# ZYNQ_PL_Bank_13.net
KiCad netlist of a schematic drawn in Altium Designer
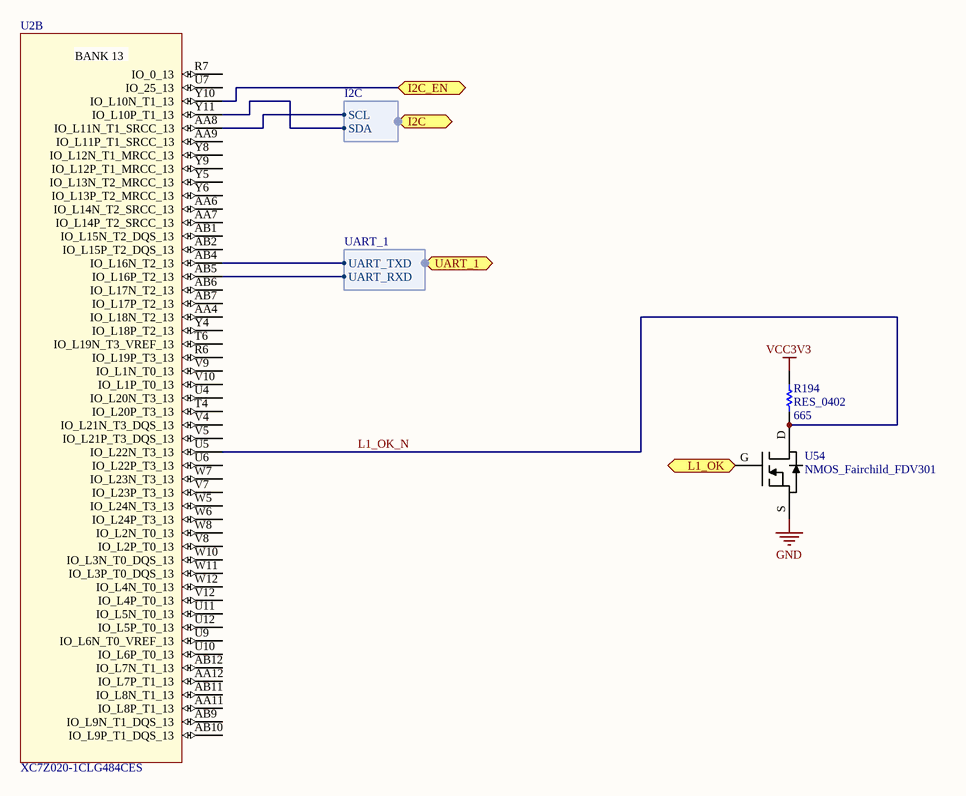
[diagram p0: ZYNQ_PL_Bank_13.SchDoc]

(export (version "E")
  (design (tool "Eeschema 10.0.6"))
  (components
    (comp (ref "R194")
      (value "RES_0402")
      (footprint "RESC0402(1005)_N")
      (description "RES 665 OHM 1/10W 1% 0402 SMD")
      (fields
        (field (name "ALTIUM_VALUE") "665")
        (field (name "PART NUMBER") "ERJ-2RKF6650X")
        (field (name "MANUFACTURER") "Panasonic Electronic Components")
      )
      (libsource (lib "COMRAD_Database") (part "RES_0402"))
    )
    (comp (ref "U2")
      (value "XC7Z020-1CLG484CES")
      (footprint "ZYNQ_xc7z020clg484pkg_BGA-484")
      (description "XC7Z020-1CLG484CES, Zynq-7000 All Programmable SoC")
      (fields (field (name "MANUFACTURER") "Xilinx"))
      (libsource (lib "COMRAD_Database") (part "ZYNQ_XC7Z020CLG484PKG"))
    )
    (comp (ref "U54")
      (value "NMOS_Fairchild_FDV301")
      (footprint "NMOS_Fairchild_FDV301_SOT23-3")
      (description "MOSFET N-CH 25V 220MA SOT-23")
      (fields (field (name "PART NUMBER") "FDV301N") (field (name "MANUFACTURER") "Fairchild Semiconductor"))
      (libsource (lib "COMRAD_Database") (part "NMOS_Fairchild_FDV301"))
    )
  )
  (nets
    (net (code "3") (name "/I2C_EN") (class "Default")
      (node (ref "U2") (pin "Y10") (pinfunction "IO_L10N_T1_13_Y10") (pintype "bidirectional"))
    )
    (net (code "4") (name "/L1_OK") (class "Default") (node (ref "U54") (pin "G") (pintype "passive")))
    (net (code "5") (name "/L1_OK_N") (class "Default")
      (node (ref "R194") (pin "1") (pinfunction "1_1") (pintype "passive"))
      (node (ref "U2") (pin "U5") (pinfunction "IO_L22N_T3_13_U5") (pintype "bidirectional"))
      (node (ref "U54") (pin "D") (pintype "passive"))
    )
    (net (code "6") (name "/SCL") (class "Default")
      (node (ref "U2") (pin "AA8") (pinfunction "IO_L11N_T1_SRCC_13_AA8") (pintype "bidirectional"))
    )
    (net (code "7") (name "/SDA") (class "Default")
      (node (ref "U2") (pin "Y11") (pinfunction "IO_L10P_T1_13_Y11") (pintype "bidirectional"))
    )
    (net (code "8") (name "/UART_RXD") (class "Default")
      (node (ref "U2") (pin "AB5") (pinfunction "IO_L16P_T2_13_AB5") (pintype "bidirectional"))
    )
    (net (code "9") (name "/UART_TXD") (class "Default")
      (node (ref "U2") (pin "AB4") (pinfunction "IO_L16N_T2_13_AB4") (pintype "bidirectional"))
    )
    (net (code "12") (name "GND") (class "Default") (node (ref "U54") (pin "S") (pintype "passive")))
    (net (code "13") (name "VCC3V3") (class "Default")
      (node (ref "R194") (pin "2") (pinfunction "2_2") (pintype "passive"))
    )
    (net (code "14") (name "unconnected-(U2B-IO_0_13-PadR7)") (class "Default")
      (node (ref "U2") (pin "R7") (pinfunction "IO_0_13_R7") (pintype "bidirectional"))
    )
    (net (code "15") (name "unconnected-(U2B-IO_25_13-PadU7)") (class "Default")
      (node (ref "U2") (pin "U7") (pinfunction "IO_25_13_U7") (pintype "bidirectional"))
    )
    (net (code "16") (name "unconnected-(U2B-IO_L1N_T0_13-PadV9)") (class "Default")
      (node (ref "U2") (pin "V9") (pinfunction "IO_L1N_T0_13_V9") (pintype "bidirectional"))
    )
    (net (code "17") (name "unconnected-(U2B-IO_L1P_T0_13-PadV10)") (class "Default")
      (node (ref "U2") (pin "V10") (pinfunction "IO_L1P_T0_13_V10") (pintype "bidirectional"))
    )
    (net (code "18") (name "unconnected-(U2B-IO_L2N_T0_13-PadW8)") (class "Default")
      (node (ref "U2") (pin "W8") (pinfunction "IO_L2N_T0_13_W8") (pintype "bidirectional"))
    )
    (net (code "19") (name "unconnected-(U2B-IO_L2P_T0_13-PadV8)") (class "Default")
      (node (ref "U2") (pin "V8") (pinfunction "IO_L2P_T0_13_V8") (pintype "bidirectional"))
    )
    (net (code "20") (name "unconnected-(U2B-IO_L3N_T0_DQS_13-PadW10)") (class "Default")
      (node (ref "U2") (pin "W10") (pinfunction "IO_L3N_T0_DQS_13_W10") (pintype "bidirectional"))
    )
    (net (code "21") (name "unconnected-(U2B-IO_L3P_T0_DQS_13-PadW11)") (class "Default")
      (node (ref "U2") (pin "W11") (pinfunction "IO_L3P_T0_DQS_13_W11") (pintype "bidirectional"))
    )
    (net (code "22") (name "unconnected-(U2B-IO_L4N_T0_13-PadW12)") (class "Default")
      (node (ref "U2") (pin "W12") (pinfunction "IO_L4N_T0_13_W12") (pintype "bidirectional"))
    )
    (net (code "23") (name "unconnected-(U2B-IO_L4P_T0_13-PadV12)") (class "Default")
      (node (ref "U2") (pin "V12") (pinfunction "IO_L4P_T0_13_V12") (pintype "bidirectional"))
    )
    (net (code "24") (name "unconnected-(U2B-IO_L5N_T0_13-PadU11)") (class "Default")
      (node (ref "U2") (pin "U11") (pinfunction "IO_L5N_T0_13_U11") (pintype "bidirectional"))
    )
    (net (code "25") (name "unconnected-(U2B-IO_L5P_T0_13-PadU12)") (class "Default")
      (node (ref "U2") (pin "U12") (pinfunction "IO_L5P_T0_13_U12") (pintype "bidirectional"))
    )
    (net (code "26") (name "unconnected-(U2B-IO_L6N_T0_VREF_13-PadU9)") (class "Default")
      (node (ref "U2") (pin "U9") (pinfunction "IO_L6N_T0_VREF_13_U9") (pintype "bidirectional"))
    )
    (net (code "27") (name "unconnected-(U2B-IO_L6P_T0_13-PadU10)") (class "Default")
      (node (ref "U2") (pin "U10") (pinfunction "IO_L6P_T0_13_U10") (pintype "bidirectional"))
    )
    (net (code "28") (name "unconnected-(U2B-IO_L7N_T1_13-PadAB12)") (class "Default")
      (node (ref "U2") (pin "AB12") (pinfunction "IO_L7N_T1_13_AB12") (pintype "bidirectional"))
    )
    (net (code "29") (name "unconnected-(U2B-IO_L7P_T1_13-PadAA12)") (class "Default")
      (node (ref "U2") (pin "AA12") (pinfunction "IO_L7P_T1_13_AA12") (pintype "bidirectional"))
    )
    (net (code "30") (name "unconnected-(U2B-IO_L8N_T1_13-PadAB11)") (class "Default")
      (node (ref "U2") (pin "AB11") (pinfunction "IO_L8N_T1_13_AB11") (pintype "bidirectional"))
    )
    (net (code "31") (name "unconnected-(U2B-IO_L8P_T1_13-PadAA11)") (class "Default")
      (node (ref "U2") (pin "AA11") (pinfunction "IO_L8P_T1_13_AA11") (pintype "bidirectional"))
    )
    (net (code "32") (name "unconnected-(U2B-IO_L9N_T1_DQS_13-PadAB9)") (class "Default")
      (node (ref "U2") (pin "AB9") (pinfunction "IO_L9N_T1_DQS_13_AB9") (pintype "bidirectional"))
    )
    (net (code "33") (name "unconnected-(U2B-IO_L9P_T1_DQS_13-PadAB10)") (class "Default")
      (node (ref "U2") (pin "AB10") (pinfunction "IO_L9P_T1_DQS_13_AB10") (pintype "bidirectional"))
    )
    (net (code "34") (name "unconnected-(U2B-IO_L11P_T1_SRCC_13-PadAA9)") (class "Default")
      (node (ref "U2") (pin "AA9") (pinfunction "IO_L11P_T1_SRCC_13_AA9") (pintype "bidirectional"))
    )
    (net (code "35") (name "unconnected-(U2B-IO_L12N_T1_MRCC_13-PadY8)") (class "Default")
      (node (ref "U2") (pin "Y8") (pinfunction "IO_L12N_T1_MRCC_13_Y8") (pintype "bidirectional"))
    )
    (net (code "36") (name "unconnected-(U2B-IO_L12P_T1_MRCC_13-PadY9)") (class "Default")
      (node (ref "U2") (pin "Y9") (pinfunction "IO_L12P_T1_MRCC_13_Y9") (pintype "bidirectional"))
    )
    (net (code "37") (name "unconnected-(U2B-IO_L13N_T2_MRCC_13-PadY5)") (class "Default")
      (node (ref "U2") (pin "Y5") (pinfunction "IO_L13N_T2_MRCC_13_Y5") (pintype "bidirectional"))
    )
    (net (code "38") (name "unconnected-(U2B-IO_L13P_T2_MRCC_13-PadY6)") (class "Default")
      (node (ref "U2") (pin "Y6") (pinfunction "IO_L13P_T2_MRCC_13_Y6") (pintype "bidirectional"))
    )
    (net (code "39") (name "unconnected-(U2B-IO_L14N_T2_SRCC_13-PadAA6)") (class "Default")
      (node (ref "U2") (pin "AA6") (pinfunction "IO_L14N_T2_SRCC_13_AA6") (pintype "bidirectional"))
    )
    (net (code "40") (name "unconnected-(U2B-IO_L14P_T2_SRCC_13-PadAA7)") (class "Default")
      (node (ref "U2") (pin "AA7") (pinfunction "IO_L14P_T2_SRCC_13_AA7") (pintype "bidirectional"))
    )
    (net (code "41") (name "unconnected-(U2B-IO_L15N_T2_DQS_13-PadAB1)") (class "Default")
      (node (ref "U2") (pin "AB1") (pinfunction "IO_L15N_T2_DQS_13_AB1") (pintype "bidirectional"))
    )
    (net (code "42") (name "unconnected-(U2B-IO_L15P_T2_DQS_13-PadAB2)") (class "Default")
      (node (ref "U2") (pin "AB2") (pinfunction "IO_L15P_T2_DQS_13_AB2") (pintype "bidirectional"))
    )
    (net (code "43") (name "unconnected-(U2B-IO_L17N_T2_13-PadAB6)") (class "Default")
      (node (ref "U2") (pin "AB6") (pinfunction "IO_L17N_T2_13_AB6") (pintype "bidirectional"))
    )
    (net (code "44") (name "unconnected-(U2B-IO_L17P_T2_13-PadAB7)") (class "Default")
      (node (ref "U2") (pin "AB7") (pinfunction "IO_L17P_T2_13_AB7") (pintype "bidirectional"))
    )
    (net (code "45") (name "unconnected-(U2B-IO_L18N_T2_13-PadAA4)") (class "Default")
      (node (ref "U2") (pin "AA4") (pinfunction "IO_L18N_T2_13_AA4") (pintype "bidirectional"))
    )
    (net (code "46") (name "unconnected-(U2B-IO_L18P_T2_13-PadY4)") (class "Default")
      (node (ref "U2") (pin "Y4") (pinfunction "IO_L18P_T2_13_Y4") (pintype "bidirectional"))
    )
    (net (code "47") (name "unconnected-(U2B-IO_L19N_T3_VREF_13-PadT6)") (class "Default")
      (node (ref "U2") (pin "T6") (pinfunction "IO_L19N_T3_VREF_13_T6") (pintype "bidirectional"))
    )
    (net (code "48") (name "unconnected-(U2B-IO_L19P_T3_13-PadR6)") (class "Default")
      (node (ref "U2") (pin "R6") (pinfunction "IO_L19P_T3_13_R6") (pintype "bidirectional"))
    )
    (net (code "49") (name "unconnected-(U2B-IO_L20N_T3_13-PadU4)") (class "Default")
      (node (ref "U2") (pin "U4") (pinfunction "IO_L20N_T3_13_U4") (pintype "bidirectional"))
    )
    (net (code "50") (name "unconnected-(U2B-IO_L20P_T3_13-PadT4)") (class "Default")
      (node (ref "U2") (pin "T4") (pinfunction "IO_L20P_T3_13_T4") (pintype "bidirectional"))
    )
    (net (code "51") (name "unconnected-(U2B-IO_L21N_T3_DQS_13-PadV4)") (class "Default")
      (node (ref "U2") (pin "V4") (pinfunction "IO_L21N_T3_DQS_13_V4") (pintype "bidirectional"))
    )
    (net (code "52") (name "unconnected-(U2B-IO_L21P_T3_DQS_13-PadV5)") (class "Default")
      (node (ref "U2") (pin "V5") (pinfunction "IO_L21P_T3_DQS_13_V5") (pintype "bidirectional"))
    )
    (net (code "53") (name "unconnected-(U2B-IO_L22P_T3_13-PadU6)") (class "Default")
      (node (ref "U2") (pin "U6") (pinfunction "IO_L22P_T3_13_U6") (pintype "bidirectional"))
    )
    (net (code "54") (name "unconnected-(U2B-IO_L23N_T3_13-PadW7)") (class "Default")
      (node (ref "U2") (pin "W7") (pinfunction "IO_L23N_T3_13_W7") (pintype "bidirectional"))
    )
    (net (code "55") (name "unconnected-(U2B-IO_L23P_T3_13-PadV7)") (class "Default")
      (node (ref "U2") (pin "V7") (pinfunction "IO_L23P_T3_13_V7") (pintype "bidirectional"))
    )
    (net (code "56") (name "unconnected-(U2B-IO_L24N_T3_13-PadW5)") (class "Default")
      (node (ref "U2") (pin "W5") (pinfunction "IO_L24N_T3_13_W5") (pintype "bidirectional"))
    )
    (net (code "57") (name "unconnected-(U2B-IO_L24P_T3_13-PadW6)") (class "Default")
      (node (ref "U2") (pin "W6") (pinfunction "IO_L24P_T3_13_W6") (pintype "bidirectional"))
    )
  )
)
